# TEMP_SCH.net
KiCad netlist of a schematic drawn in Altium Designer
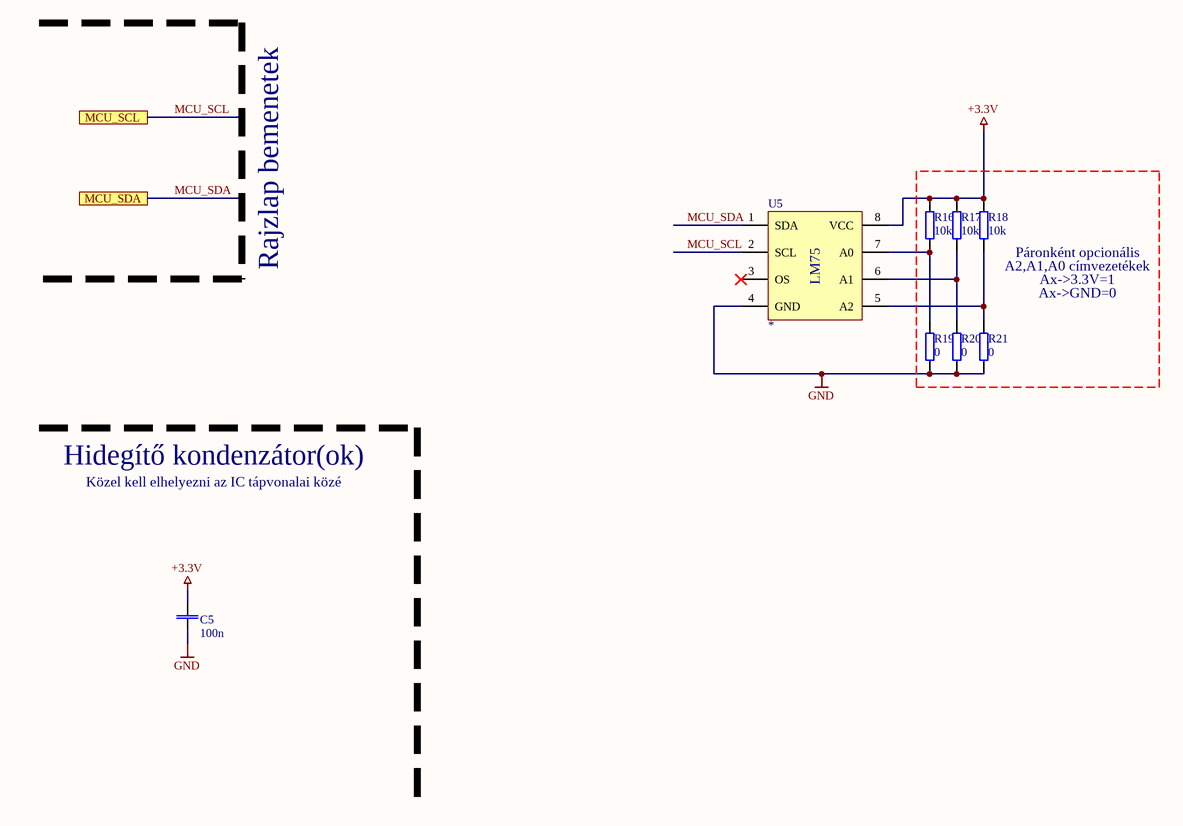
[diagram p0: TEMP_SCH.SchDoc]

(export (version "E")
  (design (tool "Eeschema 10.0.6"))
  (components
    (comp (ref "C5")
      (value "100n")
      (footprint "CAP 0805")
      (description "NON POLARIZED CAPACITOR")
      (libsource (lib "SCH_LIB") (part "CAP"))
    )
    (comp (ref "R16")
      (value "10k")
      (footprint "RES 0805")
      (description "RESISTOR")
      (libsource (lib "SCH_LIB") (part "RES"))
    )
    (comp (ref "R17")
      (value "10k")
      (footprint "RES 0805")
      (description "RESISTOR")
      (libsource (lib "SCH_LIB") (part "RES"))
    )
    (comp (ref "R18")
      (value "10k")
      (footprint "RES 0805")
      (description "RESISTOR")
      (libsource (lib "SCH_LIB") (part "RES"))
    )
    (comp (ref "R19")
      (value "0")
      (footprint "RES 0805")
      (description "RESISTOR")
      (libsource (lib "SCH_LIB") (part "RES"))
    )
    (comp (ref "R20")
      (value "0")
      (footprint "RES 0805")
      (description "RESISTOR")
      (libsource (lib "SCH_LIB") (part "RES"))
    )
    (comp (ref "R21")
      (value "0")
      (footprint "RES 0805")
      (description "RESISTOR")
      (libsource (lib "SCH_LIB") (part "RES"))
    )
    (comp (ref "U5")
      (value "*")
      (footprint "SO8")
      (description "Temperature sensor with I2C interface")
      (libsource (lib "SCH_LIB") (part "LM75"))
    )
  )
  (nets
    (net (code "1") (name "+3.3V") (class "Default")
      (node (ref "C5") (pin "2") (pinfunction "2_2") (pintype "passive"))
      (node (ref "R16") (pin "2") (pinfunction "2_2") (pintype "passive"))
      (node (ref "R17") (pin "2") (pinfunction "2_2") (pintype "passive"))
      (node (ref "R18") (pin "2") (pinfunction "2_2") (pintype "passive"))
      (node (ref "U5") (pin "8") (pinfunction "VCC_8") (pintype "passive"))
    )
    (net (code "2") (name "/MCU_SCL") (class "Default")
      (node (ref "U5") (pin "2") (pinfunction "SCL_2") (pintype "passive"))
    )
    (net (code "3") (name "/MCU_SDA") (class "Default")
      (node (ref "U5") (pin "1") (pinfunction "SDA_1") (pintype "passive"))
    )
    (net (code "4") (name "GND") (class "Default")
      (node (ref "C5") (pin "1") (pinfunction "1_1") (pintype "passive"))
      (node (ref "R19") (pin "1") (pinfunction "1_1") (pintype "passive"))
      (node (ref "R20") (pin "1") (pinfunction "1_1") (pintype "passive"))
      (node (ref "R21") (pin "1") (pinfunction "1_1") (pintype "passive"))
      (node (ref "U5") (pin "4") (pinfunction "GND_4") (pintype "passive"))
    )
    (net (code "5") (name "Net-(U5-A0)") (class "Default")
      (node (ref "R16") (pin "1") (pinfunction "1_1") (pintype "passive"))
      (node (ref "R19") (pin "2") (pinfunction "2_2") (pintype "passive"))
      (node (ref "U5") (pin "7") (pinfunction "A0_7") (pintype "passive"))
    )
    (net (code "6") (name "Net-(U5-A1)") (class "Default")
      (node (ref "R17") (pin "1") (pinfunction "1_1") (pintype "passive"))
      (node (ref "R20") (pin "2") (pinfunction "2_2") (pintype "passive"))
      (node (ref "U5") (pin "6") (pinfunction "A1_6") (pintype "passive"))
    )
    (net (code "7") (name "Net-(U5-A2)") (class "Default")
      (node (ref "R18") (pin "1") (pinfunction "1_1") (pintype "passive"))
      (node (ref "R21") (pin "2") (pinfunction "2_2") (pintype "passive"))
      (node (ref "U5") (pin "5") (pinfunction "A2_5") (pintype "passive"))
    )
    (net (code "8") (name "unconnected-(U5-OS-Pad3)") (class "Default")
      (node (ref "U5") (pin "3") (pinfunction "OS_3") (pintype "passive+no_connect"))
    )
  )
)
